# Microcontroller.net
KiCad netlist of a schematic drawn in Altium Designer
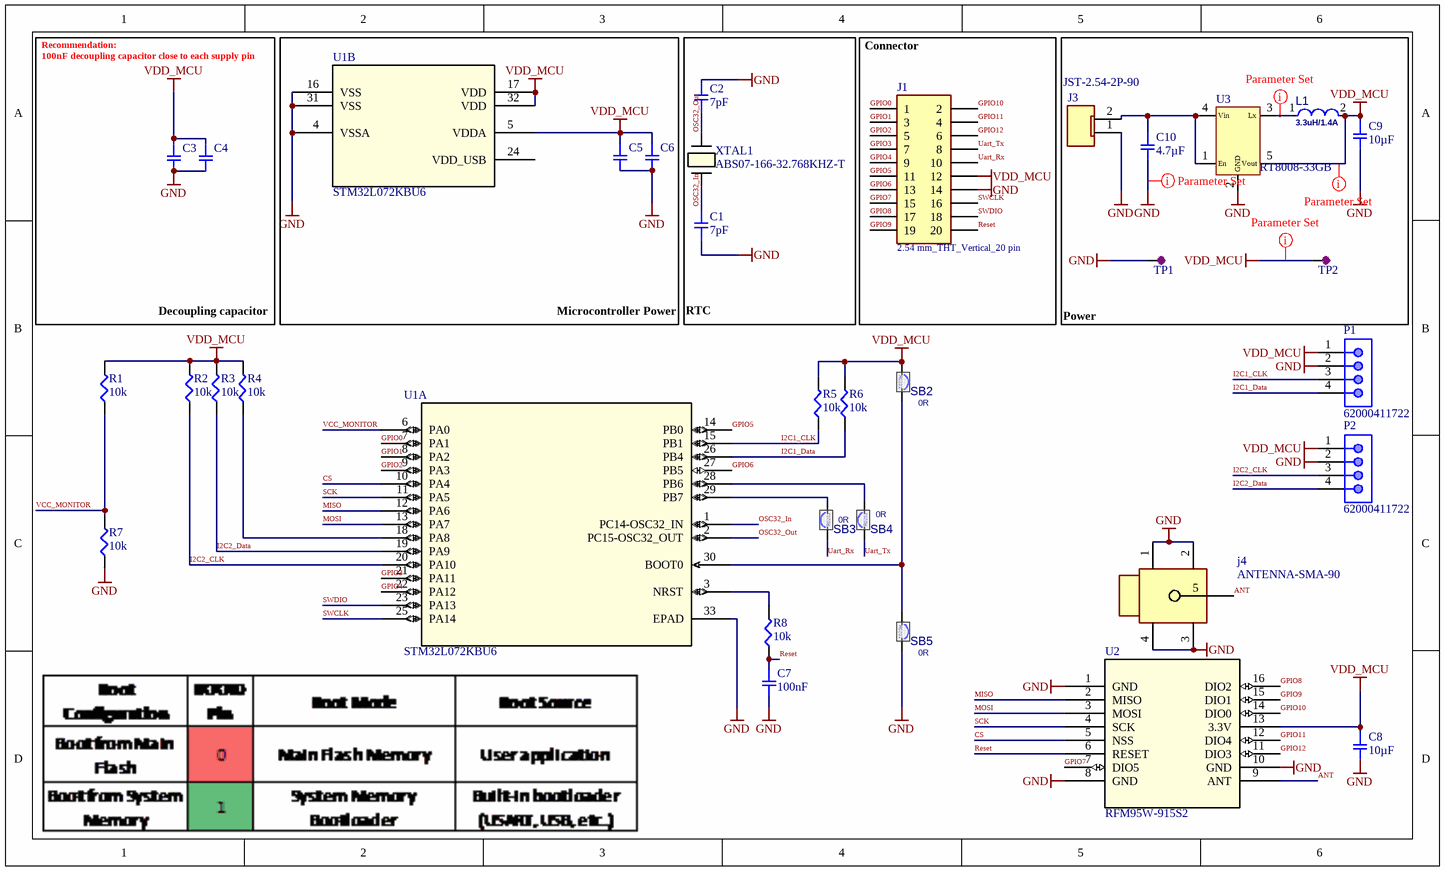
[diagram p0: Microcontroller.SchDoc]

(export (version "E")
  (design (tool "Eeschema 10.0.6"))
  (components
    (comp (ref "C1")
      (value "7pF")
      (footprint "SMD-0402C")
      (description "CAP CER 7PF 50V NP0 0402")
      (fields
        (field (name "DIGI-KEY PART NUMBER") "490-13315-1-ND")
        (field (name "PART NUMBER") "GJM1555C1H7R0DB01D")
      )
      (libsource (lib "capacitor_murata_0402") (part "GJM1555C1H7R0DB01D"))
    )
    (comp (ref "C2")
      (value "7pF")
      (footprint "SMD-0402C")
      (description "CAP CER 7PF 50V NP0 0402")
      (fields
        (field (name "DIGI-KEY PART NUMBER") "490-13315-1-ND")
        (field (name "PART NUMBER") "GJM1555C1H7R0DB01D")
      )
      (libsource (lib "capacitor_murata_0402") (part "GJM1555C1H7R0DB01D"))
    )
    (comp (ref "C3")
      (value "100nF")
      (footprint "Cap0201")
      (description "CAP CER 0.1UF 10V X5R 0201")
      (fields
        (field (name "DIGI-KEY PART NUMBER") "490-5405-1-ND")
        (field (name "PART NUMBER") "GRM033R61A104ME15D")
      )
      (libsource (lib "capacitor_murata_0201") (part "GRM033R61A104ME15D"))
    )
    (comp (ref "C4")
      (value "100nF")
      (footprint "Cap0201")
      (description "CAP CER 0.1UF 10V X5R 0201")
      (fields
        (field (name "DIGI-KEY PART NUMBER") "490-5405-1-ND")
        (field (name "PART NUMBER") "GRM033R61A104ME15D")
      )
      (libsource (lib "capacitor_murata_0201") (part "GRM033R61A104ME15D"))
    )
    (comp (ref "C5")
      (value "100nF")
      (footprint "Cap0201")
      (description "CAP CER 0.1UF 10V X5R 0201")
      (fields
        (field (name "DIGI-KEY PART NUMBER") "490-5405-1-ND")
        (field (name "PART NUMBER") "GRM033R61A104ME15D")
      )
      (libsource (lib "capacitor_murata_0201") (part "GRM033R61A104ME15D"))
    )
    (comp (ref "C6")
      (value "1µF")
      (footprint "Cap0201")
      (description "CAP CER 1UF 10V X5R 0201")
      (fields
        (field (name "DIGI-KEY PART NUMBER") "490-13226-1-ND")
        (field (name "PART NUMBER") "GRM033R61A105ME15D")
      )
      (libsource (lib "capacitor_murata_0201") (part "GRM033R61A105ME15D"))
    )
    (comp (ref "C7")
      (value "100nF")
      (footprint "Cap0201")
      (description "CAP CER 0.1UF 10V X5R 0201")
      (fields
        (field (name "DIGI-KEY PART NUMBER") "490-5405-1-ND")
        (field (name "PART NUMBER") "GRM033R61A104ME15D")
      )
      (libsource (lib "capacitor_murata_0201") (part "GRM033R61A104ME15D"))
    )
    (comp (ref "C8")
      (value "10µF")
      (footprint "SMD-0805C")
      (description "CAP CER 10UF 10V X7R 0805")
      (fields
        (field (name "DIGI-KEY PART NUMBER") "490-10919-1-ND")
        (field (name "PART NUMBER") "GRJ21BR71A106KE01L")
      )
      (libsource (lib "capacitor_murata_0805") (part "GRJ21BR71A106KE01L"))
    )
    (comp (ref "C9")
      (value "10µF")
      (footprint "SMD-0805C")
      (description "CAP CER 10UF 10V X7R 0805")
      (fields
        (field (name "DIGI-KEY PART NUMBER") "490-10919-1-ND")
        (field (name "PART NUMBER") "GRJ21BR71A106KE01L")
      )
      (libsource (lib "capacitor_murata_0805") (part "GRJ21BR71A106KE01L"))
    )
    (comp (ref "C10")
      (value "4.7µF")
      (footprint "SMD-0805C")
      (description "CAP CER 4.7UF 6.3V X5R 0805")
      (fields
        (field (name "DIGI-KEY PART NUMBER") "490-9749-1-ND")
        (field (name "PART NUMBER") "GRM21BR60J475KA11L")
      )
      (libsource (lib "capacitor_murata_0805") (part "GRM21BR60J475KA11L"))
    )
    (comp (ref "J1")
      (value "2.54 mm_THT_Vertical_20 pin")
      (footprint "61302021121")
      (description "Pin Header WR-PHD, pitch 2.54 mm, THT, Vertical, dual row, 20 pin")
      (fields (field (name "PART NUMBER") "61302021121") (field (name "PUBLISHER") "Wurth Elektronik"))
      (libsource (lib "HDR, CON") (part "61302021121"))
    )
    (comp (ref "J3")
      (value "JST-2.54-2P-90")
      (footprint "JST-2.54-2P-90")
      (description "Female Connector JST 2 Vias, 2.54mm 90º.")
      (libsource (lib "Connectors") (part "JST-2.54-2P-90"))
    )
    (comp (ref "j4")
      (value "ANTENNA-SMA-90")
      (footprint "ANTENNA-SMA-90")
      (description "Connector SMA for Antenna, 90º.")
      (libsource (lib "Connectors") (part "ANTENNA-SMA-90"))
    )
    (comp (ref "L1")
      (value "3.3uH/1.4A")
      (footprint "INDP2520x12N")
      (description "Inductor_3.3uH 20%_1.3A_SMD 25*20")
      (fields (field (name "MANF_P#") "ASPI-2515-3R3M-T2") (field (name "MANF") "Abracon LLC"))
      (libsource (lib "IND, CHOK, BUZZER") (part "ASPI-2515-3R3M-T2"))
    )
    (comp (ref "P1")
      (value "62000411722")
      (footprint "62000411722")
      (description "WR-WTB THT Male Horizontal Shrouded Header, pitch 2mm, 4p")
      (fields (field (name "PUBLISHER") "Wurth Elektronik"))
      (libsource (lib "HDR, CON") (part "62000411722"))
    )
    (comp (ref "P2")
      (value "62000411722")
      (footprint "62000411722")
      (description "WR-WTB THT Male Horizontal Shrouded Header, pitch 2mm, 4p")
      (fields (field (name "PUBLISHER") "Wurth Elektronik"))
      (libsource (lib "HDR, CON") (part "62000411722"))
    )
    (comp (ref "R1")
      (value "10k")
      (footprint "Res0201")
      (description "RES SMD 10K OHM 1% 1/20W 0201")
      (fields
        (field (name "PART NUMBER") "ERJ-1GEF1002C")
        (field (name "DIGI-KEY PART NUMBER") "P10.0KABCT-ND")
      )
      (libsource (lib "Panasonic_ERJ_0201") (part "ERJ-1GEF1002C"))
    )
    (comp (ref "R2")
      (value "10k")
      (footprint "Res0201")
      (description "RES SMD 10K OHM 1% 1/20W 0201")
      (fields
        (field (name "PART NUMBER") "ERJ-1GEF1002C")
        (field (name "DIGI-KEY PART NUMBER") "P10.0KABCT-ND")
      )
      (libsource (lib "Panasonic_ERJ_0201") (part "ERJ-1GEF1002C"))
    )
    (comp (ref "R3")
      (value "10k")
      (footprint "Res0201")
      (description "RES SMD 10K OHM 1% 1/20W 0201")
      (fields
        (field (name "PART NUMBER") "ERJ-1GEF1002C")
        (field (name "DIGI-KEY PART NUMBER") "P10.0KABCT-ND")
      )
      (libsource (lib "Panasonic_ERJ_0201") (part "ERJ-1GEF1002C"))
    )
    (comp (ref "R4")
      (value "10k")
      (footprint "Res0201")
      (description "RES SMD 10K OHM 1% 1/20W 0201")
      (fields
        (field (name "PART NUMBER") "ERJ-1GEF1002C")
        (field (name "DIGI-KEY PART NUMBER") "P10.0KABCT-ND")
      )
      (libsource (lib "Panasonic_ERJ_0201") (part "ERJ-1GEF1002C"))
    )
    (comp (ref "R5")
      (value "10k")
      (footprint "Res0201")
      (description "RES SMD 10K OHM 1% 1/20W 0201")
      (fields
        (field (name "PART NUMBER") "ERJ-1GEF1002C")
        (field (name "DIGI-KEY PART NUMBER") "P10.0KABCT-ND")
      )
      (libsource (lib "Panasonic_ERJ_0201") (part "ERJ-1GEF1002C"))
    )
    (comp (ref "R6")
      (value "10k")
      (footprint "Res0201")
      (description "RES SMD 10K OHM 1% 1/20W 0201")
      (fields
        (field (name "PART NUMBER") "ERJ-1GEF1002C")
        (field (name "DIGI-KEY PART NUMBER") "P10.0KABCT-ND")
      )
      (libsource (lib "Panasonic_ERJ_0201") (part "ERJ-1GEF1002C"))
    )
    (comp (ref "R7")
      (value "10k")
      (footprint "Res0201")
      (description "RES SMD 10K OHM 1% 1/20W 0201")
      (fields
        (field (name "PART NUMBER") "ERJ-1GEF1002C")
        (field (name "DIGI-KEY PART NUMBER") "P10.0KABCT-ND")
      )
      (libsource (lib "Panasonic_ERJ_0201") (part "ERJ-1GEF1002C"))
    )
    (comp (ref "R8")
      (value "10k")
      (footprint "Res0201")
      (description "RES SMD 10K OHM 1% 1/20W 0201")
      (fields
        (field (name "PART NUMBER") "ERJ-1GEF1002C")
        (field (name "DIGI-KEY PART NUMBER") "P10.0KABCT-ND")
      )
      (libsource (lib "Panasonic_ERJ_0201") (part "ERJ-1GEF1002C"))
    )
    (comp (ref "SB2")
      (value "0R")
      (footprint "Res0201")
      (description "RES_0 Ohm_ Jumper_1/16W_SMD 0402")
      (fields (field (name "MANF_P#") "RC0402JR-070RL") (field (name "MANF") "Yageo"))
      (libsource (lib "") (part "RC0201JR-070RL_1"))
    )
    (comp (ref "SB3")
      (value "0R")
      (footprint "Res0201")
      (description "RES_0 Ohm_ Jumper_1/16W_SMD 0402")
      (fields (field (name "MANF_P#") "RC0402JR-070RL") (field (name "MANF") "Yageo"))
      (libsource (lib "RES") (part "RC0201JR-070RL"))
    )
    (comp (ref "SB4")
      (value "0R")
      (footprint "Res0201")
      (description "RES_0 Ohm_ Jumper_1/16W_SMD 0402")
      (fields (field (name "MANF_P#") "RC0402JR-070RL") (field (name "MANF") "Yageo"))
      (libsource (lib "RES") (part "RC0201JR-070RL"))
    )
    (comp (ref "SB5")
      (value "0R")
      (footprint "Res0201")
      (description "RES_0 Ohm_ Jumper_1/16W_SMD 0402")
      (fields (field (name "MANF_P#") "RC0402JR-070RL") (field (name "MANF") "Yageo"))
      (libsource (lib "") (part "RC0201JR-070RL_1"))
    )
    (comp (ref "TP1")
      (value "TPSMD_25mil")
      (footprint "TPSMD_25mil")
      (libsource (lib "SIGN, BDIAGRAM") (part "TPSMD_25mil"))
    )
    (comp (ref "TP2")
      (value "TPSMD_25mil")
      (footprint "TPSMD_25mil")
      (libsource (lib "SIGN, BDIAGRAM") (part "TPSMD_25mil"))
    )
    (comp (ref "U1")
      (value "STM32L072KBU6")
      (footprint "UFQFPN32-5x5mm-L")
      (description "No Description Available")
      (libsource (lib "STM32L072KBU6") (part "STM32L072KBU6"))
    )
    (comp (ref "U2")
      (value "RFM95W-915S2")
      (footprint "IC16_RFM95W-915S2_RFS")
      (description "Description")
      (fields (field (name "COPYRIGHT") "Copyright (C) 2025 Ultra Librarian. All rights reserved."))
      (libsource (lib "RFM95W-915S2") (part "RFM95W-915S2"))
    )
    (comp (ref "U3")
      (value "RT8008-33GB")
      (footprint "SOT23, 5")
      (libsource (lib "RT8008-33GB") (part "RT8008-33GB"))
    )
    (comp (ref "XTAL1")
      (value "ABS07-166-32.768KHZ-T")
      (footprint "XTAL_ABS07-166-32.768KHZ-T_ABR")
      (description "Description")
      (fields (field (name "COPYRIGHT") "Copyright (C) 2025 Ultra Librarian. All rights reserved."))
      (libsource (lib "ABS07-166-32P768KHZ-T") (part "ABS07-166-32.768KHZ-T"))
    )
  )
  (nets
    (net (code "1") (name "/ANT") (class "Default")
      (node (ref "U2") (pin "9") (pinfunction "ANT_9") (pintype "passive"))
      (node (ref "j4") (pin "5") (pintype "passive"))
    )
    (net (code "2") (name "/CS") (class "Default")
      (node (ref "U1") (pin "10") (pinfunction "PA4_10") (pintype "bidirectional"))
      (node (ref "U2") (pin "5") (pinfunction "NSS_5") (pintype "passive"))
    )
    (net (code "3") (name "/GPIO0") (class "Default")
      (node (ref "J1") (pin "1") (pinfunction "1_1") (pintype "passive"))
      (node (ref "U1") (pin "7") (pinfunction "PA1_7") (pintype "bidirectional"))
    )
    (net (code "4") (name "/GPIO1") (class "Default")
      (node (ref "J1") (pin "3") (pinfunction "3_3") (pintype "passive"))
      (node (ref "U1") (pin "8") (pinfunction "PA2_8") (pintype "bidirectional"))
    )
    (net (code "5") (name "/GPIO2") (class "Default")
      (node (ref "J1") (pin "5") (pinfunction "5_5") (pintype "passive"))
      (node (ref "U1") (pin "9") (pinfunction "PA3_9") (pintype "bidirectional"))
    )
    (net (code "6") (name "/GPIO3") (class "Default")
      (node (ref "J1") (pin "7") (pinfunction "7_7") (pintype "passive"))
      (node (ref "U1") (pin "21") (pinfunction "PA11_21") (pintype "bidirectional"))
    )
    (net (code "7") (name "/GPIO4") (class "Default")
      (node (ref "J1") (pin "9") (pinfunction "9_9") (pintype "passive"))
      (node (ref "U1") (pin "22") (pinfunction "PA12_22") (pintype "bidirectional"))
    )
    (net (code "8") (name "/GPIO5") (class "Default")
      (node (ref "J1") (pin "11") (pinfunction "11_11") (pintype "passive"))
      (node (ref "U1") (pin "14") (pinfunction "PB0_14") (pintype "bidirectional"))
    )
    (net (code "9") (name "/GPIO6") (class "Default")
      (node (ref "J1") (pin "13") (pinfunction "13_13") (pintype "passive"))
      (node (ref "U1") (pin "27") (pinfunction "PB5_27") (pintype "bidirectional"))
    )
    (net (code "10") (name "/GPIO7") (class "Default")
      (node (ref "J1") (pin "15") (pinfunction "15_15") (pintype "passive"))
      (node (ref "U2") (pin "7") (pinfunction "DIO5_7") (pintype "bidirectional"))
    )
    (net (code "11") (name "/GPIO8") (class "Default")
      (node (ref "J1") (pin "17") (pinfunction "17_17") (pintype "passive"))
      (node (ref "U2") (pin "16") (pinfunction "DIO2_16") (pintype "bidirectional"))
    )
    (net (code "12") (name "/GPIO9") (class "Default")
      (node (ref "J1") (pin "19") (pinfunction "19_19") (pintype "passive"))
      (node (ref "U2") (pin "15") (pinfunction "DIO1_15") (pintype "bidirectional"))
    )
    (net (code "13") (name "/GPIO10") (class "Default")
      (node (ref "J1") (pin "2") (pinfunction "2_2") (pintype "passive"))
      (node (ref "U2") (pin "14") (pinfunction "DIO0_14") (pintype "bidirectional"))
    )
    (net (code "14") (name "/GPIO11") (class "Default")
      (node (ref "J1") (pin "4") (pinfunction "4_4") (pintype "passive"))
      (node (ref "U2") (pin "12") (pinfunction "DIO4_12") (pintype "bidirectional"))
    )
    (net (code "15") (name "/GPIO12") (class "Default")
      (node (ref "J1") (pin "6") (pinfunction "6_6") (pintype "passive"))
      (node (ref "U2") (pin "11") (pinfunction "DIO3_11") (pintype "bidirectional"))
    )
    (net (code "16") (name "/I2C1_CLK") (class "Default")
      (node (ref "P1") (pin "3") (pinfunction "3_3") (pintype "passive"))
      (node (ref "R5") (pin "1") (pinfunction "1_1") (pintype "passive"))
      (node (ref "U1") (pin "15") (pinfunction "PB1_15") (pintype "bidirectional"))
    )
    (net (code "17") (name "/I2C1_Data") (class "Default")
      (node (ref "P1") (pin "4") (pinfunction "4_4") (pintype "passive"))
      (node (ref "R6") (pin "1") (pinfunction "1_1") (pintype "passive"))
      (node (ref "U1") (pin "26") (pinfunction "PB4_26") (pintype "bidirectional"))
    )
    (net (code "18") (name "/I2C2_CLK") (class "Default")
      (node (ref "P2") (pin "3") (pinfunction "3_3") (pintype "passive"))
      (node (ref "R2") (pin "1") (pinfunction "1_1") (pintype "passive"))
      (node (ref "U1") (pin "20") (pinfunction "PA10_20") (pintype "bidirectional"))
    )
    (net (code "19") (name "/I2C2_Data") (class "Default")
      (node (ref "P2") (pin "4") (pinfunction "4_4") (pintype "passive"))
      (node (ref "R3") (pin "1") (pinfunction "1_1") (pintype "passive"))
      (node (ref "U1") (pin "19") (pinfunction "PA9_19") (pintype "bidirectional"))
    )
    (net (code "20") (name "/MISO") (class "Default")
      (node (ref "U1") (pin "12") (pinfunction "PA6_12") (pintype "bidirectional"))
      (node (ref "U2") (pin "2") (pinfunction "MISO_2") (pintype "passive"))
    )
    (net (code "21") (name "/MOSI") (class "Default")
      (node (ref "U1") (pin "13") (pinfunction "PA7_13") (pintype "bidirectional"))
      (node (ref "U2") (pin "3") (pinfunction "MOSI_3") (pintype "passive"))
    )
    (net (code "22") (name "/OSC32_In") (class "Default")
      (node (ref "C1") (pin "2") (pinfunction "2_2") (pintype "passive"))
      (node (ref "U1") (pin "1") (pinfunction "PC14-OSC32_IN_1") (pintype "bidirectional"))
      (node (ref "XTAL1") (pin "2") (pinfunction "2_2") (pintype "passive"))
    )
    (net (code "23") (name "/OSC32_Out") (class "Default")
      (node (ref "C2") (pin "1") (pinfunction "1_1") (pintype "passive"))
      (node (ref "U1") (pin "2") (pinfunction "PC15-OSC32_OUT_2") (pintype "bidirectional"))
      (node (ref "XTAL1") (pin "1") (pinfunction "1_1") (pintype "passive"))
    )
    (net (code "24") (name "/Reset") (class "Default")
      (node (ref "C7") (pin "1") (pinfunction "1_1") (pintype "passive"))
      (node (ref "J1") (pin "20") (pinfunction "20_20") (pintype "passive"))
      (node (ref "R8") (pin "1") (pinfunction "1_1") (pintype "passive"))
      (node (ref "U2") (pin "6") (pinfunction "RESET_6") (pintype "passive"))
    )
    (net (code "25") (name "/SCK") (class "Default")
      (node (ref "U1") (pin "11") (pinfunction "PA5_11") (pintype "bidirectional"))
      (node (ref "U2") (pin "4") (pinfunction "SCK_4") (pintype "passive"))
    )
    (net (code "26") (name "/SWCLK") (class "Default")
      (node (ref "J1") (pin "16") (pinfunction "16_16") (pintype "passive"))
      (node (ref "U1") (pin "25") (pinfunction "PA14_25") (pintype "bidirectional"))
    )
    (net (code "27") (name "/SWDIO") (class "Default")
      (node (ref "J1") (pin "18") (pinfunction "18_18") (pintype "passive"))
      (node (ref "U1") (pin "23") (pinfunction "PA13_23") (pintype "bidirectional"))
    )
    (net (code "28") (name "/Uart_Rx") (class "Default")
      (node (ref "J1") (pin "10") (pinfunction "10_10") (pintype "passive"))
      (node (ref "SB3") (pin "2") (pintype "passive"))
    )
    (net (code "29") (name "/Uart_Tx") (class "Default")
      (node (ref "J1") (pin "8") (pinfunction "8_8") (pintype "passive"))
      (node (ref "SB4") (pin "2") (pintype "passive"))
    )
    (net (code "30") (name "/VCC_MONITOR") (class "Default")
      (node (ref "R1") (pin "1") (pinfunction "1_1") (pintype "passive"))
      (node (ref "R7") (pin "2") (pinfunction "2_2") (pintype "passive"))
      (node (ref "U1") (pin "6") (pinfunction "PA0_6") (pintype "bidirectional"))
    )
    (net (code "31") (name "GND") (class "Default")
      (node (ref "C1") (pin "1") (pinfunction "1_1") (pintype "passive"))
      (node (ref "C10") (pin "2") (pinfunction "2_2") (pintype "passive"))
      (node (ref "C2") (pin "2") (pinfunction "2_2") (pintype "passive"))
      (node (ref "C3") (pin "2") (pinfunction "2_2") (pintype "passive"))
      (node (ref "C4") (pin "2") (pinfunction "2_2") (pintype "passive"))
      (node (ref "C5") (pin "2") (pinfunction "2_2") (pintype "passive"))
      (node (ref "C6") (pin "2") (pinfunction "2_2") (pintype "passive"))
      (node (ref "C7") (pin "2") (pinfunction "2_2") (pintype "passive"))
      (node (ref "C8") (pin "2") (pinfunction "2_2") (pintype "passive"))
      (node (ref "C9") (pin "2") (pinfunction "2_2") (pintype "passive"))
      (node (ref "J1") (pin "14") (pinfunction "14_14") (pintype "passive"))
      (node (ref "J3") (pin "1") (pintype "passive"))
      (node (ref "P1") (pin "2") (pinfunction "2_2") (pintype "passive"))
      (node (ref "P2") (pin "2") (pinfunction "2_2") (pintype "passive"))
      (node (ref "R7") (pin "1") (pinfunction "1_1") (pintype "passive"))
      (node (ref "SB5") (pin "1") (pintype "passive"))
      (node (ref "TP1") (pin "1") (pinfunction "1_1") (pintype "passive"))
      (node (ref "U1") (pin "16") (pinfunction "VSS_16") (pintype "power_in"))
      (node (ref "U1") (pin "31") (pinfunction "VSS_31") (pintype "power_in"))
      (node (ref "U1") (pin "33") (pinfunction "EPAD_33") (pintype "passive"))
      (node (ref "U1") (pin "4") (pinfunction "VSSA_4") (pintype "power_in"))
      (node (ref "U2") (pin "1") (pinfunction "GND_1") (pintype "power_in"))
      (node (ref "U2") (pin "10") (pinfunction "GND_10") (pintype "power_in"))
      (node (ref "U2") (pin "8") (pinfunction "GND_8") (pintype "power_in"))
      (node (ref "U3") (pin "2") (pinfunction "GND_2") (pintype "passive"))
      (node (ref "j4") (pin "1") (pintype "passive"))
      (node (ref "j4") (pin "2") (pintype "passive"))
      (node (ref "j4") (pin "3") (pintype "passive"))
      (node (ref "j4") (pin "4") (pintype "passive"))
    )
    (net (code "32") (name "Net-(U1A-BOOT0)") (class "Default")
      (node (ref "SB2") (pin "1") (pintype "passive"))
      (node (ref "SB5") (pin "2") (pintype "passive"))
      (node (ref "U1") (pin "30") (pinfunction "BOOT0_30") (pintype "input"))
    )
    (net (code "33") (name "Net-(U1A-NRST)") (class "Default")
      (node (ref "R8") (pin "2") (pinfunction "2_2") (pintype "passive"))
      (node (ref "U1") (pin "3") (pinfunction "NRST_3") (pintype "bidirectional"))
    )
    (net (code "34") (name "Net-(U1A-PA8)") (class "Default")
      (node (ref "R4") (pin "1") (pinfunction "1_1") (pintype "passive"))
      (node (ref "U1") (pin "18") (pinfunction "PA8_18") (pintype "bidirectional"))
    )
    (net (code "35") (name "Net-(U1A-PB6)") (class "Default")
      (node (ref "SB4") (pin "1") (pintype "passive"))
      (node (ref "U1") (pin "28") (pinfunction "PB6_28") (pintype "bidirectional"))
    )
    (net (code "36") (name "Net-(U1A-PB7)") (class "Default")
      (node (ref "SB3") (pin "1") (pintype "passive"))
      (node (ref "U1") (pin "29") (pinfunction "PB7_29") (pintype "bidirectional"))
    )
    (net (code "37") (name "Net-(U3-En)") (class "Default")
      (node (ref "C10") (pin "1") (pinfunction "1_1") (pintype "passive"))
      (node (ref "J3") (pin "2") (pintype "passive"))
      (node (ref "U3") (pin "1") (pinfunction "En_1") (pintype "passive"))
      (node (ref "U3") (pin "4") (pinfunction "Vin_4") (pintype "passive"))
    )
    (net (code "38") (name "Net-(U3-Lx)") (class "Default")
      (node (ref "L1") (pin "1") (pinfunction "1_1") (pintype "passive"))
      (node (ref "U3") (pin "3") (pinfunction "Lx_3") (pintype "passive"))
    )
    (net (code "39") (name "VDD_MCU") (class "Default")
      (node (ref "C3") (pin "1") (pinfunction "1_1") (pintype "passive"))
      (node (ref "C4") (pin "1") (pinfunction "1_1") (pintype "passive"))
      (node (ref "C5") (pin "1") (pinfunction "1_1") (pintype "passive"))
      (node (ref "C6") (pin "1") (pinfunction "1_1") (pintype "passive"))
      (node (ref "C8") (pin "1") (pinfunction "1_1") (pintype "passive"))
      (node (ref "C9") (pin "1") (pinfunction "1_1") (pintype "passive"))
      (node (ref "J1") (pin "12") (pinfunction "12_12") (pintype "passive"))
      (node (ref "L1") (pin "2") (pinfunction "2_2") (pintype "passive"))
      (node (ref "P1") (pin "1") (pinfunction "1_1") (pintype "passive"))
      (node (ref "P2") (pin "1") (pinfunction "1_1") (pintype "passive"))
      (node (ref "R1") (pin "2") (pinfunction "2_2") (pintype "passive"))
      (node (ref "R2") (pin "2") (pinfunction "2_2") (pintype "passive"))
      (node (ref "R3") (pin "2") (pinfunction "2_2") (pintype "passive"))
      (node (ref "R4") (pin "2") (pinfunction "2_2") (pintype "passive"))
      (node (ref "R5") (pin "2") (pinfunction "2_2") (pintype "passive"))
      (node (ref "R6") (pin "2") (pinfunction "2_2") (pintype "passive"))
      (node (ref "SB2") (pin "2") (pintype "passive"))
      (node (ref "TP2") (pin "1") (pinfunction "1_1") (pintype "passive"))
      (node (ref "U1") (pin "17") (pinfunction "VDD_17") (pintype "power_in"))
      (node (ref "U1") (pin "32") (pinfunction "VDD_32") (pintype "power_in"))
      (node (ref "U1") (pin "5") (pinfunction "VDDA_5") (pintype "power_in"))
      (node (ref "U2") (pin "13") (pinfunction "3.3V_13") (pintype "passive"))
      (node (ref "U3") (pin "5") (pinfunction "Vout_5") (pintype "passive"))
    )
    (net (code "40") (name "unconnected-(U1B-VDD_USB-Pad24)") (class "Default")
      (node (ref "U1") (pin "24") (pinfunction "VDD_USB_24") (pintype "power_in"))
    )
  )
)
